# valve.net
KiCad netlist of a schematic drawn in Altium Designer
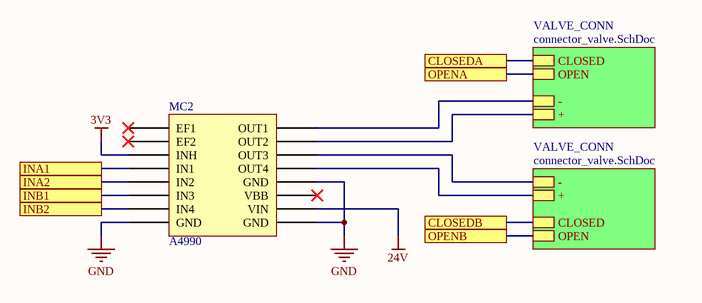
[diagram p0: valve.SchDoc]

(export (version "E")
  (design (tool "Eeschema 10.0.6"))
  (components
    (comp (ref "MC2")
      (value "A4990")
      (footprint "A4990 Dual Motor Driver Carrier")
      (libsource (lib "brew_lib") (part "A4990 Dual Motor Driver Carrier"))
    )
  )
  (nets
    (net (code "1") (name "/+") (class "Default")
      (node (ref "MC2") (pin "15") (pinfunction "OUT2_15") (pintype "passive"))
    )
    (net (code "2") (name "/+_1") (class "Default")
      (node (ref "MC2") (pin "13") (pinfunction "OUT4_13") (pintype "passive"))
    )
    (net (code "3") (name "/-") (class "Default")
      (node (ref "MC2") (pin "16") (pinfunction "OUT1_16") (pintype "passive"))
    )
    (net (code "4") (name "/-_1") (class "Default")
      (node (ref "MC2") (pin "14") (pinfunction "OUT3_14") (pintype "passive"))
    )
    (net (code "7") (name "/INA1") (class "Default")
      (node (ref "MC2") (pin "4") (pinfunction "IN1_4") (pintype "passive"))
    )
    (net (code "8") (name "/INA2") (class "Default")
      (node (ref "MC2") (pin "5") (pinfunction "IN2_5") (pintype "passive"))
    )
    (net (code "9") (name "/INB1") (class "Default")
      (node (ref "MC2") (pin "6") (pinfunction "IN3_6") (pintype "passive"))
    )
    (net (code "10") (name "/INB2") (class "Default")
      (node (ref "MC2") (pin "7") (pinfunction "IN4_7") (pintype "passive"))
    )
    (net (code "13") (name "3V3") (class "Default")
      (node (ref "MC2") (pin "3") (pinfunction "INH_3") (pintype "passive"))
    )
    (net (code "14") (name "24V") (class "Default")
      (node (ref "MC2") (pin "10") (pinfunction "VIN_10") (pintype "passive"))
    )
    (net (code "15") (name "GND") (class "Default")
      (node (ref "MC2") (pin "12") (pinfunction "GND_12") (pintype "passive"))
      (node (ref "MC2") (pin "8") (pinfunction "GND_8") (pintype "passive"))
      (node (ref "MC2") (pin "9") (pinfunction "GND_9") (pintype "passive"))
    )
    (net (code "16") (name "unconnected-(MC2-EF1-Pad1)") (class "Default")
      (node (ref "MC2") (pin "1") (pinfunction "EF1_1") (pintype "passive+no_connect"))
    )
    (net (code "17") (name "unconnected-(MC2-EF2-Pad2)") (class "Default")
      (node (ref "MC2") (pin "2") (pinfunction "EF2_2") (pintype "passive+no_connect"))
    )
    (net (code "18") (name "unconnected-(MC2-VBB-Pad11)") (class "Default")
      (node (ref "MC2") (pin "11") (pinfunction "VBB_11") (pintype "passive+no_connect"))
    )
  )
)
